# transboard.net
KiCad netlist of a schematic drawn in Altium Designer
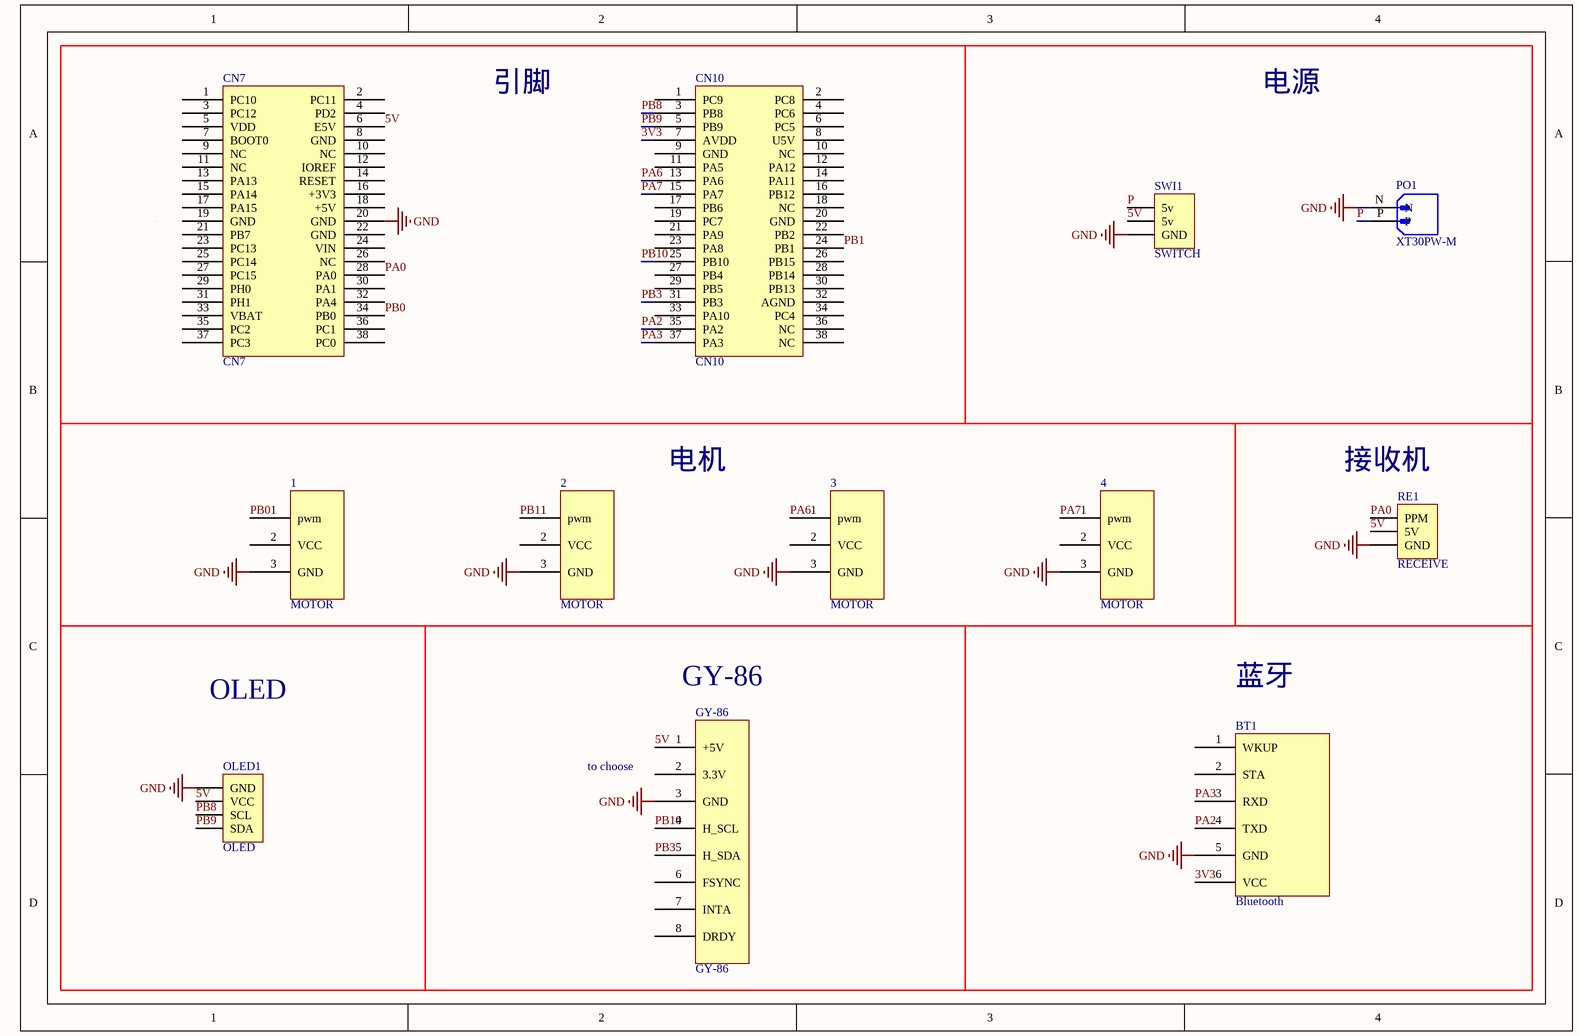
[diagram p0: transboard.SchDoc]

(export (version "E")
  (design (tool "Eeschema 10.0.6"))
  (components
    (comp (ref "1") (value "MOTOR") (footprint "M") (libsource (lib "Free Documents") (part "M")))
    (comp (ref "2") (value "MOTOR") (footprint "M") (libsource (lib "Free Documents") (part "M")))
    (comp (ref "3") (value "MOTOR") (footprint "M") (libsource (lib "Free Documents") (part "M")))
    (comp (ref "4") (value "MOTOR") (footprint "M") (libsource (lib "Free Documents") (part "M")))
    (comp (ref "BT1")
      (value "Bluetooth")
      (footprint "Bluetooth")
      (libsource (lib "Free Documents") (part "Bluetooth"))
    )
    (comp (ref "CN7") (value "CN7") (footprint "CN7") (libsource (lib "Free Documents") (part "CN7")))
    (comp (ref "CN10") (value "CN10") (footprint "CN10") (libsource (lib "Free Documents") (part "CN10")))
    (comp (ref "GY-86") (value "GY-86") (footprint "HDR1X8") (libsource (lib "转接板lib") (part "GY-86")))
    (comp (ref "OLED1")
      (value "OLED")
      (footprint "HDR1X4")
      (description "Header, 4-Pin")
      (fields (field (name "PUBLISHER") "Altium Limited"))
      (libsource (lib "Free Documents") (part "Header 4"))
    )
    (comp (ref "PO1")
      (value "XT30PW-M")
      (footprint "AMASS_XT30PW-M")
      (description "Socket; DC supply; XT30; male; PIN: 2; on PCBs; THT; Colour: yellow")
      (fields (field (name "MF") "AMASS"))
      (libsource (lib "Free Documents") (part "XT30PW-M"))
    )
    (comp (ref "RE1")
      (value "RECEIVE")
      (footprint "HDR1X3")
      (description "Header, 3-Pin")
      (fields (field (name "PUBLISHER") "Altium Limited"))
      (libsource (lib "Free Documents") (part "Header 3"))
    )
    (comp (ref "SWI1")
      (value "SWITCH")
      (footprint "HDR1X3")
      (description "Header, 3-Pin")
      (fields (field (name "PUBLISHER") "Altium Limited"))
      (libsource (lib "Free Documents") (part "Header 3_1"))
    )
  )
  (nets
    (net (code "1") (name "/3V3") (class "Default")
      (node (ref "BT1") (pin "6") (pinfunction "VCC_6") (pintype "passive"))
      (node (ref "CN10") (pin "7") (pinfunction "AVDD_7") (pintype "passive"))
    )
    (net (code "2") (name "/5V") (class "Default")
      (node (ref "CN7") (pin "6") (pinfunction "E5V_6") (pintype "passive"))
      (node (ref "GY-86") (pin "1") (pinfunction "+5V_1") (pintype "passive"))
      (node (ref "OLED1") (pin "2") (pinfunction "VCC_2") (pintype "passive"))
      (node (ref "RE1") (pin "2") (pinfunction "5V_2") (pintype "passive"))
      (node (ref "SWI1") (pin "2") (pinfunction "5v_2") (pintype "passive"))
    )
    (net (code "4") (name "/P") (class "Default")
      (node (ref "PO1") (pin "P") (pinfunction "P_P") (pintype "power_in"))
      (node (ref "SWI1") (pin "1") (pinfunction "5v_1") (pintype "passive"))
    )
    (net (code "5") (name "/PA0") (class "Default")
      (node (ref "CN7") (pin "28") (pinfunction "PA0_28") (pintype "passive"))
      (node (ref "RE1") (pin "1") (pinfunction "PPM_1") (pintype "passive"))
    )
    (net (code "6") (name "/PA2") (class "Default")
      (node (ref "BT1") (pin "4") (pinfunction "TXD_4") (pintype "passive"))
      (node (ref "CN10") (pin "35") (pinfunction "PA2_35") (pintype "passive"))
    )
    (net (code "7") (name "/PA3") (class "Default")
      (node (ref "BT1") (pin "3") (pinfunction "RXD_3") (pintype "passive"))
      (node (ref "CN10") (pin "37") (pinfunction "PA3_37") (pintype "passive"))
    )
    (net (code "8") (name "/PA6") (class "Default")
      (node (ref "3") (pin "1") (pinfunction "pwm_1") (pintype "passive"))
      (node (ref "CN10") (pin "13") (pinfunction "PA6_13") (pintype "passive"))
    )
    (net (code "9") (name "/PA7") (class "Default")
      (node (ref "4") (pin "1") (pinfunction "pwm_1") (pintype "passive"))
      (node (ref "CN10") (pin "15") (pinfunction "PA7_15") (pintype "passive"))
    )
    (net (code "10") (name "/PB0") (class "Default")
      (node (ref "1") (pin "1") (pinfunction "pwm_1") (pintype "passive"))
      (node (ref "CN7") (pin "34") (pinfunction "PB0_34") (pintype "passive"))
    )
    (net (code "11") (name "/PB1") (class "Default")
      (node (ref "2") (pin "1") (pinfunction "pwm_1") (pintype "passive"))
      (node (ref "CN10") (pin "24") (pinfunction "PB1_24") (pintype "passive"))
    )
    (net (code "12") (name "/PB3") (class "Default")
      (node (ref "CN10") (pin "31") (pinfunction "PB3_31") (pintype "passive"))
      (node (ref "GY-86") (pin "5") (pinfunction "H_SDA_5") (pintype "passive"))
    )
    (net (code "13") (name "/PB8") (class "Default")
      (node (ref "CN10") (pin "3") (pinfunction "PB8_3") (pintype "passive"))
      (node (ref "OLED1") (pin "3") (pinfunction "SCL_3") (pintype "passive"))
    )
    (net (code "14") (name "/PB9") (class "Default")
      (node (ref "CN10") (pin "5") (pinfunction "PB9_5") (pintype "passive"))
      (node (ref "OLED1") (pin "4") (pinfunction "SDA_4") (pintype "passive"))
    )
    (net (code "15") (name "/PB10") (class "Default")
      (node (ref "CN10") (pin "25") (pinfunction "PB10_25") (pintype "passive"))
      (node (ref "GY-86") (pin "4") (pinfunction "H_SCL_4") (pintype "passive"))
    )
    (net (code "16") (name "GND") (class "Default")
      (node (ref "1") (pin "3") (pinfunction "GND_3") (pintype "passive"))
      (node (ref "2") (pin "3") (pinfunction "GND_3") (pintype "passive"))
      (node (ref "3") (pin "3") (pinfunction "GND_3") (pintype "passive"))
      (node (ref "4") (pin "3") (pinfunction "GND_3") (pintype "passive"))
      (node (ref "BT1") (pin "5") (pinfunction "GND_5") (pintype "passive"))
      (node (ref "CN7") (pin "20") (pinfunction "GND_20") (pintype "passive"))
      (node (ref "GY-86") (pin "3") (pinfunction "GND_3") (pintype "passive"))
      (node (ref "OLED1") (pin "1") (pinfunction "GND_1") (pintype "passive"))
      (node (ref "PO1") (pin "N") (pinfunction "N_N") (pintype "power_in"))
      (node (ref "RE1") (pin "3") (pinfunction "GND_3") (pintype "passive"))
      (node (ref "SWI1") (pin "3") (pinfunction "GND_3") (pintype "passive"))
    )
    (net (code "17") (name "unconnected-(1-VCC-Pad2)") (class "Default")
      (node (ref "1") (pin "2") (pinfunction "VCC_2") (pintype "passive"))
    )
    (net (code "18") (name "unconnected-(2-VCC-Pad2)") (class "Default")
      (node (ref "2") (pin "2") (pinfunction "VCC_2") (pintype "passive"))
    )
    (net (code "19") (name "unconnected-(3-VCC-Pad2)") (class "Default")
      (node (ref "3") (pin "2") (pinfunction "VCC_2") (pintype "passive"))
    )
    (net (code "20") (name "unconnected-(4-VCC-Pad2)") (class "Default")
      (node (ref "4") (pin "2") (pinfunction "VCC_2") (pintype "passive"))
    )
    (net (code "21") (name "unconnected-(BT1-STA-Pad2)") (class "Default")
      (node (ref "BT1") (pin "2") (pinfunction "STA_2") (pintype "passive"))
    )
    (net (code "22") (name "unconnected-(BT1-WKUP-Pad1)") (class "Default")
      (node (ref "BT1") (pin "1") (pinfunction "WKUP_1") (pintype "passive"))
    )
    (net (code "23") (name "unconnected-(CN7-+3V3-Pad16)") (class "Default")
      (node (ref "CN7") (pin "16") (pinfunction "+3V3_16") (pintype "passive"))
    )
    (net (code "24") (name "unconnected-(CN7-+5V-Pad18)") (class "Default")
      (node (ref "CN7") (pin "18") (pinfunction "+5V_18") (pintype "passive"))
    )
    (net (code "25") (name "unconnected-(CN7-BOOT0-Pad7)") (class "Default")
      (node (ref "CN7") (pin "7") (pinfunction "BOOT0_7") (pintype "passive"))
    )
    (net (code "26") (name "unconnected-(CN7-GND-Pad8)") (class "Default")
      (node (ref "CN7") (pin "8") (pinfunction "GND_8") (pintype "passive"))
    )
    (net (code "27") (name "unconnected-(CN7-GND-Pad19)") (class "Default")
      (node (ref "CN7") (pin "19") (pinfunction "GND_19") (pintype "passive"))
    )
    (net (code "28") (name "unconnected-(CN7-GND-Pad22)") (class "Default")
      (node (ref "CN7") (pin "22") (pinfunction "GND_22") (pintype "passive"))
    )
    (net (code "29") (name "unconnected-(CN7-IOREF-Pad12)") (class "Default")
      (node (ref "CN7") (pin "12") (pinfunction "IOREF_12") (pintype "passive"))
    )
    (net (code "30") (name "unconnected-(CN7-NC-Pad9)") (class "Default")
      (node (ref "CN7") (pin "9") (pinfunction "NC_9") (pintype "passive"))
    )
    (net (code "31") (name "unconnected-(CN7-NC-Pad10)") (class "Default")
      (node (ref "CN7") (pin "10") (pinfunction "NC_10") (pintype "passive"))
    )
    (net (code "32") (name "unconnected-(CN7-NC-Pad11)") (class "Default")
      (node (ref "CN7") (pin "11") (pinfunction "NC_11") (pintype "passive"))
    )
    (net (code "33") (name "unconnected-(CN7-NC-Pad26)") (class "Default")
      (node (ref "CN7") (pin "26") (pinfunction "NC_26") (pintype "passive"))
    )
    (net (code "34") (name "unconnected-(CN7-PA1-Pad30)") (class "Default")
      (node (ref "CN7") (pin "30") (pinfunction "PA1_30") (pintype "passive"))
    )
    (net (code "35") (name "unconnected-(CN7-PA4-Pad32)") (class "Default")
      (node (ref "CN7") (pin "32") (pinfunction "PA4_32") (pintype "passive"))
    )
    (net (code "36") (name "unconnected-(CN7-PA13-Pad13)") (class "Default")
      (node (ref "CN7") (pin "13") (pinfunction "PA13_13") (pintype "passive"))
    )
    (net (code "37") (name "unconnected-(CN7-PA14-Pad15)") (class "Default")
      (node (ref "CN7") (pin "15") (pinfunction "PA14_15") (pintype "passive"))
    )
    (net (code "38") (name "unconnected-(CN7-PA15-Pad17)") (class "Default")
      (node (ref "CN7") (pin "17") (pinfunction "PA15_17") (pintype "passive"))
    )
    (net (code "39") (name "unconnected-(CN7-PB7-Pad21)") (class "Default")
      (node (ref "CN7") (pin "21") (pinfunction "PB7_21") (pintype "passive"))
    )
    (net (code "40") (name "unconnected-(CN7-PC0-Pad38)") (class "Default")
      (node (ref "CN7") (pin "38") (pinfunction "PC0_38") (pintype "passive"))
    )
    (net (code "41") (name "unconnected-(CN7-PC1-Pad36)") (class "Default")
      (node (ref "CN7") (pin "36") (pinfunction "PC1_36") (pintype "passive"))
    )
    (net (code "42") (name "unconnected-(CN7-PC2-Pad35)") (class "Default")
      (node (ref "CN7") (pin "35") (pinfunction "PC2_35") (pintype "passive"))
    )
    (net (code "43") (name "unconnected-(CN7-PC3-Pad37)") (class "Default")
      (node (ref "CN7") (pin "37") (pinfunction "PC3_37") (pintype "passive"))
    )
    (net (code "44") (name "unconnected-(CN7-PC10-Pad1)") (class "Default")
      (node (ref "CN7") (pin "1") (pinfunction "PC10_1") (pintype "passive"))
    )
    (net (code "45") (name "unconnected-(CN7-PC11-Pad2)") (class "Default")
      (node (ref "CN7") (pin "2") (pinfunction "PC11_2") (pintype "passive"))
    )
    (net (code "46") (name "unconnected-(CN7-PC12-Pad3)") (class "Default")
      (node (ref "CN7") (pin "3") (pinfunction "PC12_3") (pintype "passive"))
    )
    (net (code "47") (name "unconnected-(CN7-PC13-Pad23)") (class "Default")
      (node (ref "CN7") (pin "23") (pinfunction "PC13_23") (pintype "passive"))
    )
    (net (code "48") (name "unconnected-(CN7-PC14-Pad25)") (class "Default")
      (node (ref "CN7") (pin "25") (pinfunction "PC14_25") (pintype "passive"))
    )
    (net (code "49") (name "unconnected-(CN7-PC15-Pad27)") (class "Default")
      (node (ref "CN7") (pin "27") (pinfunction "PC15_27") (pintype "passive"))
    )
    (net (code "50") (name "unconnected-(CN7-PD2-Pad4)") (class "Default")
      (node (ref "CN7") (pin "4") (pinfunction "PD2_4") (pintype "passive"))
    )
    (net (code "51") (name "unconnected-(CN7-PH0-Pad29)") (class "Default")
      (node (ref "CN7") (pin "29") (pinfunction "PH0_29") (pintype "passive"))
    )
    (net (code "52") (name "unconnected-(CN7-PH1-Pad31)") (class "Default")
      (node (ref "CN7") (pin "31") (pinfunction "PH1_31") (pintype "passive"))
    )
    (net (code "53") (name "unconnected-(CN7-RESET-Pad14)") (class "Default")
      (node (ref "CN7") (pin "14") (pinfunction "RESET_14") (pintype "passive"))
    )
    (net (code "54") (name "unconnected-(CN7-VBAT-Pad33)") (class "Default")
      (node (ref "CN7") (pin "33") (pinfunction "VBAT_33") (pintype "passive"))
    )
    (net (code "55") (name "unconnected-(CN7-VDD-Pad5)") (class "Default")
      (node (ref "CN7") (pin "5") (pinfunction "VDD_5") (pintype "passive"))
    )
    (net (code "56") (name "unconnected-(CN7-VIN-Pad24)") (class "Default")
      (node (ref "CN7") (pin "24") (pinfunction "VIN_24") (pintype "passive"))
    )
    (net (code "57") (name "unconnected-(CN10-AGND-Pad32)") (class "Default")
      (node (ref "CN10") (pin "32") (pinfunction "AGND_32") (pintype "passive"))
    )
    (net (code "58") (name "unconnected-(CN10-GND-Pad9)") (class "Default")
      (node (ref "CN10") (pin "9") (pinfunction "GND_9") (pintype "passive"))
    )
    (net (code "59") (name "unconnected-(CN10-GND-Pad20)") (class "Default")
      (node (ref "CN10") (pin "20") (pinfunction "GND_20") (pintype "passive"))
    )
    (net (code "60") (name "unconnected-(CN10-NC-Pad10)") (class "Default")
      (node (ref "CN10") (pin "10") (pinfunction "NC_10") (pintype "passive"))
    )
    (net (code "61") (name "unconnected-(CN10-NC-Pad18)") (class "Default")
      (node (ref "CN10") (pin "18") (pinfunction "NC_18") (pintype "passive"))
    )
    (net (code "62") (name "unconnected-(CN10-NC-Pad36)") (class "Default")
      (node (ref "CN10") (pin "36") (pinfunction "NC_36") (pintype "passive"))
    )
    (net (code "63") (name "unconnected-(CN10-NC-Pad38)") (class "Default")
      (node (ref "CN10") (pin "38") (pinfunction "NC_38") (pintype "passive"))
    )
    (net (code "64") (name "unconnected-(CN10-PA5-Pad11)") (class "Default")
      (node (ref "CN10") (pin "11") (pinfunction "PA5_11") (pintype "passive"))
    )
    (net (code "65") (name "unconnected-(CN10-PA8-Pad23)") (class "Default")
      (node (ref "CN10") (pin "23") (pinfunction "PA8_23") (pintype "passive"))
    )
    (net (code "66") (name "unconnected-(CN10-PA9-Pad21)") (class "Default")
      (node (ref "CN10") (pin "21") (pinfunction "PA9_21") (pintype "passive"))
    )
    (net (code "67") (name "unconnected-(CN10-PA10-Pad33)") (class "Default")
      (node (ref "CN10") (pin "33") (pinfunction "PA10_33") (pintype "passive"))
    )
    (net (code "68") (name "unconnected-(CN10-PA11-Pad14)") (class "Default")
      (node (ref "CN10") (pin "14") (pinfunction "PA11_14") (pintype "passive"))
    )
    (net (code "69") (name "unconnected-(CN10-PA12-Pad12)") (class "Default")
      (node (ref "CN10") (pin "12") (pinfunction "PA12_12") (pintype "passive"))
    )
    (net (code "70") (name "unconnected-(CN10-PB2-Pad22)") (class "Default")
      (node (ref "CN10") (pin "22") (pinfunction "PB2_22") (pintype "passive"))
    )
    (net (code "71") (name "unconnected-(CN10-PB4-Pad27)") (class "Default")
      (node (ref "CN10") (pin "27") (pinfunction "PB4_27") (pintype "passive"))
    )
    (net (code "72") (name "unconnected-(CN10-PB5-Pad29)") (class "Default")
      (node (ref "CN10") (pin "29") (pinfunction "PB5_29") (pintype "passive"))
    )
    (net (code "73") (name "unconnected-(CN10-PB6-Pad17)") (class "Default")
      (node (ref "CN10") (pin "17") (pinfunction "PB6_17") (pintype "passive"))
    )
    (net (code "74") (name "unconnected-(CN10-PB12-Pad16)") (class "Default")
      (node (ref "CN10") (pin "16") (pinfunction "PB12_16") (pintype "passive"))
    )
    (net (code "75") (name "unconnected-(CN10-PB13-Pad30)") (class "Default")
      (node (ref "CN10") (pin "30") (pinfunction "PB13_30") (pintype "passive"))
    )
    (net (code "76") (name "unconnected-(CN10-PB14-Pad28)") (class "Default")
      (node (ref "CN10") (pin "28") (pinfunction "PB14_28") (pintype "passive"))
    )
    (net (code "77") (name "unconnected-(CN10-PB15-Pad26)") (class "Default")
      (node (ref "CN10") (pin "26") (pinfunction "PB15_26") (pintype "passive"))
    )
    (net (code "78") (name "unconnected-(CN10-PC4-Pad34)") (class "Default")
      (node (ref "CN10") (pin "34") (pinfunction "PC4_34") (pintype "passive"))
    )
    (net (code "79") (name "unconnected-(CN10-PC5-Pad6)") (class "Default")
      (node (ref "CN10") (pin "6") (pinfunction "PC5_6") (pintype "passive"))
    )
    (net (code "80") (name "unconnected-(CN10-PC6-Pad4)") (class "Default")
      (node (ref "CN10") (pin "4") (pinfunction "PC6_4") (pintype "passive"))
    )
    (net (code "81") (name "unconnected-(CN10-PC7-Pad19)") (class "Default")
      (node (ref "CN10") (pin "19") (pinfunction "PC7_19") (pintype "passive"))
    )
    (net (code "82") (name "unconnected-(CN10-PC8-Pad2)") (class "Default")
      (node (ref "CN10") (pin "2") (pinfunction "PC8_2") (pintype "passive"))
    )
    (net (code "83") (name "unconnected-(CN10-PC9-Pad1)") (class "Default")
      (node (ref "CN10") (pin "1") (pinfunction "PC9_1") (pintype "passive"))
    )
    (net (code "84") (name "unconnected-(CN10-U5V-Pad8)") (class "Default")
      (node (ref "CN10") (pin "8") (pinfunction "U5V_8") (pintype "passive"))
    )
    (net (code "85") (name "unconnected-(GY-86-3.3V-Pad2)") (class "Default")
      (node (ref "GY-86") (pin "2") (pinfunction "3.3V_2") (pintype "passive"))
    )
    (net (code "86") (name "unconnected-(GY-86-DRDY-Pad8)") (class "Default")
      (node (ref "GY-86") (pin "8") (pinfunction "DRDY_8") (pintype "passive"))
    )
    (net (code "87") (name "unconnected-(GY-86-FSYNC-Pad6)") (class "Default")
      (node (ref "GY-86") (pin "6") (pinfunction "FSYNC_6") (pintype "passive"))
    )
    (net (code "88") (name "unconnected-(GY-86-INTA-Pad7)") (class "Default")
      (node (ref "GY-86") (pin "7") (pinfunction "INTA_7") (pintype "passive"))
    )
  )
)
